# proto1.net
KiCad netlist of a schematic drawn in EAGLE
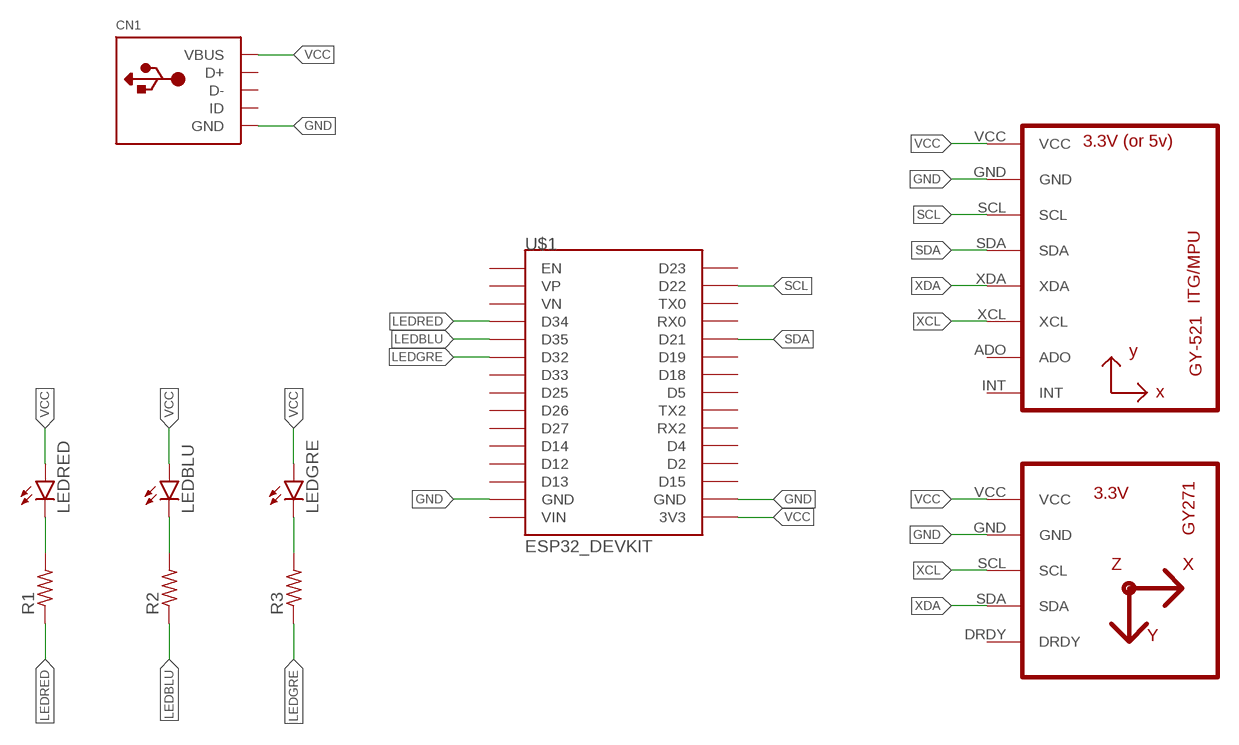
[diagram p0: schematic, sheet 1]

(export (version "E")
  (design (tool "Eeschema 10.0.6"))
  (components
    (comp (ref "CN1")
      (value "USBTHM")
      (footprint "eagle-import:USB-MINIB-THM")
      (libsource (lib "eagle-import") (part "USBTHM"))
    )
    (comp (ref "LEDBLU")
      (value "LED5MM")
      (footprint "eagle-import:LED5MM")
      (libsource (lib "eagle-import") (part "LED5MM"))
    )
    (comp (ref "LEDGRE")
      (value "LED5MM")
      (footprint "eagle-import:LED5MM")
      (libsource (lib "eagle-import") (part "LED5MM"))
    )
    (comp (ref "LEDRED")
      (value "LED5MM")
      (footprint "eagle-import:LED5MM")
      (libsource (lib "eagle-import") (part "LED5MM"))
    )
    (comp (ref "R1")
      (value "R-US_0207/10")
      (footprint "eagle-import:0207_10")
      (libsource (lib "eagle-import") (part "R-US_0207/10"))
    )
    (comp (ref "R2")
      (value "R-US_0207/10")
      (footprint "eagle-import:0207_10")
      (libsource (lib "eagle-import") (part "R-US_0207/10"))
    )
    (comp (ref "R3")
      (value "R-US_0207/10")
      (footprint "eagle-import:0207_10")
      (libsource (lib "eagle-import") (part "R-US_0207/10"))
    )
    (comp (ref "U$1")
      (value "ESP32_DEVKIT")
      (footprint "eagle-import:ESP32_DEVKIT")
      (libsource (lib "eagle-import") (part "ESP32_DEVKIT"))
    )
    (comp (ref "U2")
      (value "GY-521MPU6050")
      (footprint "eagle-import:GY-521")
      (libsource (lib "eagle-import") (part "GY-521MPU6050"))
    )
    (comp (ref "U3")
      (value "HMC5883LGY-271")
      (footprint "eagle-import:GY-271")
      (libsource (lib "eagle-import") (part "HMC5883LGY-271"))
    )
  )
  (nets
    (net (code "1") (name "GND") (class "Default")
      (node (ref "CN1") (pin "GND") (pinfunction "GND_GND") (pintype "power_in"))
      (node (ref "U$1") (pin "GND@1") (pinfunction "GND_GND@1") (pintype "bidirectional"))
      (node (ref "U$1") (pin "GND@2") (pinfunction "GND_GND@2") (pintype "bidirectional"))
      (node (ref "U2") (pin "GND") (pinfunction "GND_GND") (pintype "bidirectional"))
      (node (ref "U3") (pin "GND") (pinfunction "GND_GND") (pintype "bidirectional"))
    )
    (net (code "2") (name "LEDBLU") (class "Default")
      (node (ref "R2") (pin "1") (pinfunction "1_1") (pintype "passive"))
      (node (ref "U$1") (pin "D35") (pinfunction "D35_D35") (pintype "bidirectional"))
    )
    (net (code "3") (name "LEDGRE") (class "Default")
      (node (ref "R3") (pin "1") (pinfunction "1_1") (pintype "passive"))
      (node (ref "U$1") (pin "D32") (pinfunction "D32_D32") (pintype "bidirectional"))
    )
    (net (code "4") (name "LEDRED") (class "Default")
      (node (ref "R1") (pin "1") (pinfunction "1_1") (pintype "passive"))
      (node (ref "U$1") (pin "D34") (pinfunction "D34_D34") (pintype "bidirectional"))
    )
    (net (code "5") (name "Net-(LEDBLU-C)") (class "Default")
      (node (ref "LEDBLU") (pin "K") (pinfunction "C_K") (pintype "passive"))
      (node (ref "R2") (pin "2") (pinfunction "2_2") (pintype "passive"))
    )
    (net (code "6") (name "Net-(LEDGRE-C)") (class "Default")
      (node (ref "LEDGRE") (pin "K") (pinfunction "C_K") (pintype "passive"))
      (node (ref "R3") (pin "2") (pinfunction "2_2") (pintype "passive"))
    )
    (net (code "7") (name "Net-(LEDRED-C)") (class "Default")
      (node (ref "LEDRED") (pin "K") (pinfunction "C_K") (pintype "passive"))
      (node (ref "R1") (pin "2") (pinfunction "2_2") (pintype "passive"))
    )
    (net (code "8") (name "SCL") (class "Default")
      (node (ref "U$1") (pin "D22") (pinfunction "D22_D22") (pintype "bidirectional"))
      (node (ref "U2") (pin "SCL") (pinfunction "SCL_SCL") (pintype "bidirectional"))
    )
    (net (code "9") (name "SDA") (class "Default")
      (node (ref "U$1") (pin "D21") (pinfunction "D21_D21") (pintype "bidirectional"))
      (node (ref "U2") (pin "SDA") (pinfunction "SDA_SDA") (pintype "bidirectional"))
    )
    (net (code "10") (name "VCC") (class "Default")
      (node (ref "CN1") (pin "VBUS") (pinfunction "VBUS_VBUS") (pintype "power_in"))
      (node (ref "LEDBLU") (pin "A") (pinfunction "A_A") (pintype "passive"))
      (node (ref "LEDGRE") (pin "A") (pinfunction "A_A") (pintype "passive"))
      (node (ref "LEDRED") (pin "A") (pinfunction "A_A") (pintype "passive"))
      (node (ref "U$1") (pin "3V3") (pinfunction "3V3_3V3") (pintype "bidirectional"))
      (node (ref "U2") (pin "VCC") (pinfunction "VCC_VCC") (pintype "bidirectional"))
      (node (ref "U3") (pin "VCC") (pinfunction "VCC_VCC") (pintype "bidirectional"))
    )
    (net (code "11") (name "XCL") (class "Default")
      (node (ref "U2") (pin "XCL") (pinfunction "XCL_XCL") (pintype "bidirectional"))
      (node (ref "U3") (pin "SCL") (pinfunction "SCL_SCL") (pintype "bidirectional"))
    )
    (net (code "12") (name "XDA") (class "Default")
      (node (ref "U2") (pin "XDA") (pinfunction "XDA_XDA") (pintype "bidirectional"))
      (node (ref "U3") (pin "SDA") (pinfunction "SDA_SDA") (pintype "bidirectional"))
    )
    (net (code "13") (name "unconnected-(CN1-PadD+)") (class "Default")
      (node (ref "CN1") (pin "D+") (pinfunction "D+_D+") (pintype "bidirectional"))
    )
    (net (code "14") (name "unconnected-(CN1-PadD-)") (class "Default")
      (node (ref "CN1") (pin "D-") (pinfunction "D-_D-") (pintype "bidirectional"))
    )
    (net (code "15") (name "unconnected-(CN1-PadID)") (class "Default")
      (node (ref "CN1") (pin "ID") (pinfunction "ID_ID") (pintype "bidirectional"))
    )
    (net (code "16") (name "unconnected-(U$1-PadD2)") (class "Default")
      (node (ref "U$1") (pin "D2") (pinfunction "D2_D2") (pintype "bidirectional"))
    )
    (net (code "17") (name "unconnected-(U$1-PadD4)") (class "Default")
      (node (ref "U$1") (pin "D4") (pinfunction "D4_D4") (pintype "bidirectional"))
    )
    (net (code "18") (name "unconnected-(U$1-PadD5)") (class "Default")
      (node (ref "U$1") (pin "D5") (pinfunction "D5_D5") (pintype "bidirectional"))
    )
    (net (code "19") (name "unconnected-(U$1-PadD12)") (class "Default")
      (node (ref "U$1") (pin "D12") (pinfunction "D12_D12") (pintype "bidirectional"))
    )
    (net (code "20") (name "unconnected-(U$1-PadD13)") (class "Default")
      (node (ref "U$1") (pin "D13") (pinfunction "D13_D13") (pintype "bidirectional"))
    )
    (net (code "21") (name "unconnected-(U$1-PadD14)") (class "Default")
      (node (ref "U$1") (pin "D14") (pinfunction "D14_D14") (pintype "bidirectional"))
    )
    (net (code "22") (name "unconnected-(U$1-PadD15)") (class "Default")
      (node (ref "U$1") (pin "D15") (pinfunction "D15_D15") (pintype "bidirectional"))
    )
    (net (code "23") (name "unconnected-(U$1-PadD18)") (class "Default")
      (node (ref "U$1") (pin "D18") (pinfunction "D18_D18") (pintype "bidirectional"))
    )
    (net (code "24") (name "unconnected-(U$1-PadD19)") (class "Default")
      (node (ref "U$1") (pin "D19") (pinfunction "D19_D19") (pintype "bidirectional"))
    )
    (net (code "25") (name "unconnected-(U$1-PadD23)") (class "Default")
      (node (ref "U$1") (pin "D23") (pinfunction "D23_D23") (pintype "bidirectional"))
    )
    (net (code "26") (name "unconnected-(U$1-PadD25)") (class "Default")
      (node (ref "U$1") (pin "D25") (pinfunction "D25_D25") (pintype "bidirectional"))
    )
    (net (code "27") (name "unconnected-(U$1-PadD26)") (class "Default")
      (node (ref "U$1") (pin "D26") (pinfunction "D26_D26") (pintype "bidirectional"))
    )
    (net (code "28") (name "unconnected-(U$1-PadD27)") (class "Default")
      (node (ref "U$1") (pin "D27") (pinfunction "D27_D27") (pintype "bidirectional"))
    )
    (net (code "29") (name "unconnected-(U$1-PadD33)") (class "Default")
      (node (ref "U$1") (pin "D33") (pinfunction "D33_D33") (pintype "bidirectional"))
    )
    (net (code "30") (name "unconnected-(U$1-PadEN)") (class "Default")
      (node (ref "U$1") (pin "EN") (pinfunction "EN_EN") (pintype "bidirectional"))
    )
    (net (code "31") (name "unconnected-(U$1-PadRX0)") (class "Default")
      (node (ref "U$1") (pin "RX0") (pinfunction "RX0_RX0") (pintype "bidirectional"))
    )
    (net (code "32") (name "unconnected-(U$1-PadRX2)") (class "Default")
      (node (ref "U$1") (pin "RX2") (pinfunction "RX2_RX2") (pintype "bidirectional"))
    )
    (net (code "33") (name "unconnected-(U$1-PadTX0)") (class "Default")
      (node (ref "U$1") (pin "TX0") (pinfunction "TX0_TX0") (pintype "bidirectional"))
    )
    (net (code "34") (name "unconnected-(U$1-PadTX2)") (class "Default")
      (node (ref "U$1") (pin "TX2") (pinfunction "TX2_TX2") (pintype "bidirectional"))
    )
    (net (code "35") (name "unconnected-(U$1-PadVIN)") (class "Default")
      (node (ref "U$1") (pin "VIN") (pinfunction "VIN_VIN") (pintype "bidirectional"))
    )
    (net (code "36") (name "unconnected-(U$1-PadVN)") (class "Default")
      (node (ref "U$1") (pin "VN") (pinfunction "VN_VN") (pintype "bidirectional"))
    )
    (net (code "37") (name "unconnected-(U$1-PadVP)") (class "Default")
      (node (ref "U$1") (pin "VP") (pinfunction "VP_VP") (pintype "bidirectional"))
    )
    (net (code "38") (name "unconnected-(U2-PadADO)") (class "Default")
      (node (ref "U2") (pin "ADO") (pinfunction "ADO_ADO") (pintype "bidirectional"))
    )
    (net (code "39") (name "unconnected-(U2-PadINT)") (class "Default")
      (node (ref "U2") (pin "INT") (pinfunction "INT_INT") (pintype "bidirectional"))
    )
    (net (code "40") (name "unconnected-(U3-PadDRDY)") (class "Default")
      (node (ref "U3") (pin "DRDY") (pinfunction "DRDY_DRDY") (pintype "bidirectional"))
    )
  )
)
